# MainMCU.net
KiCad netlist of a schematic drawn in Altium Designer
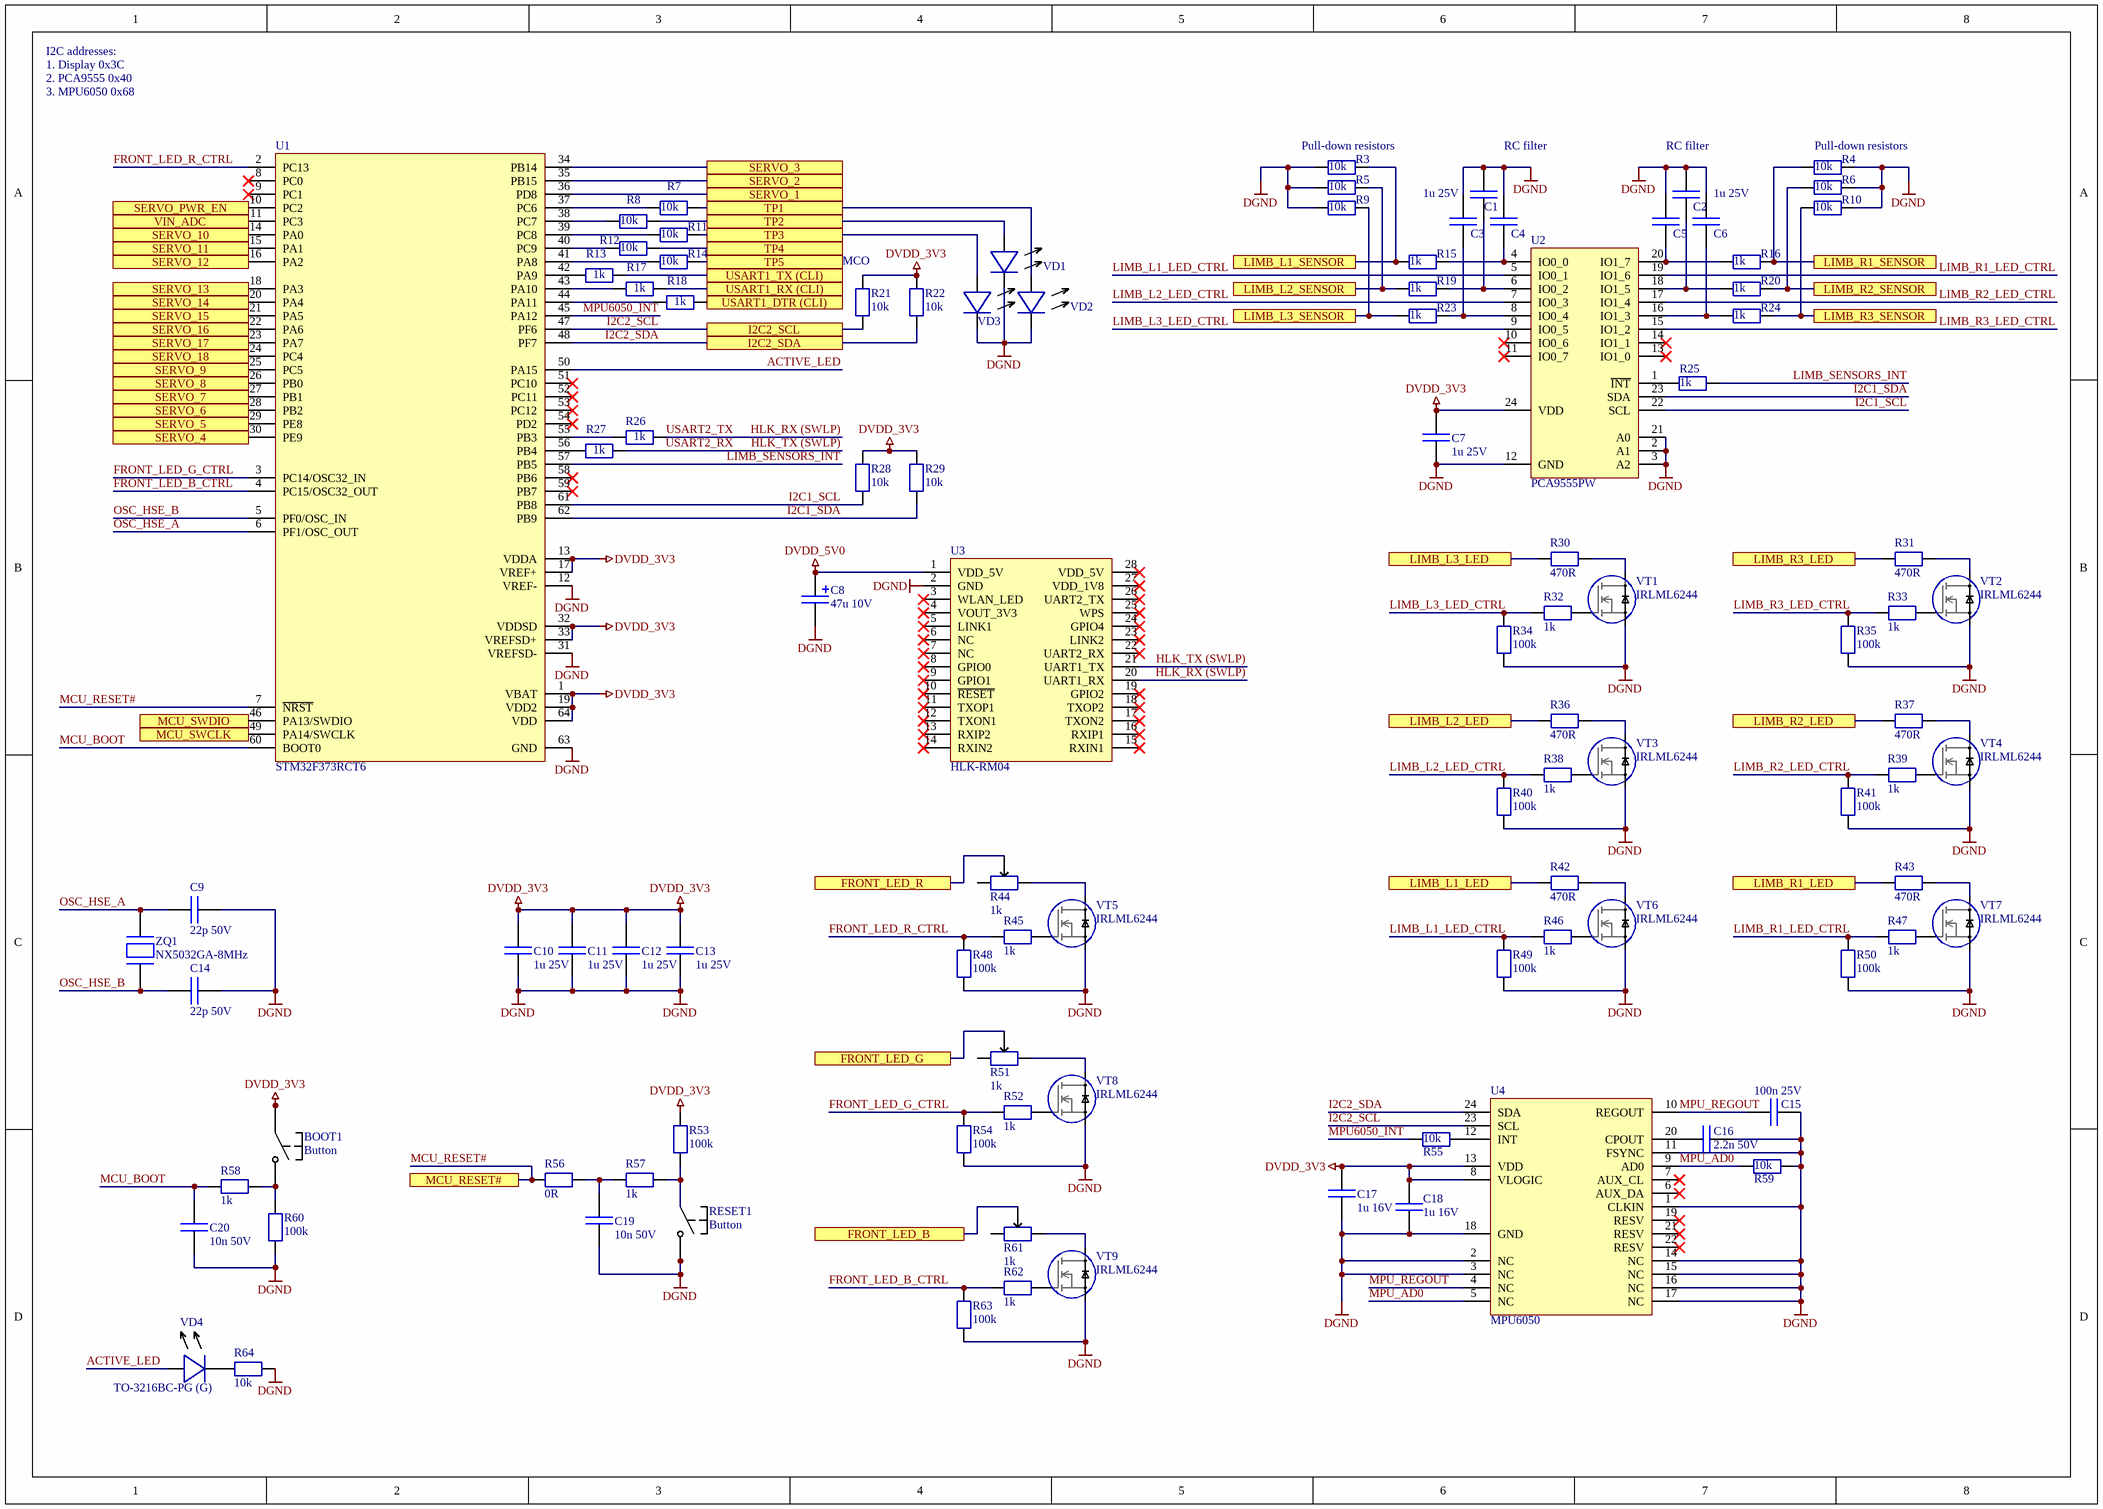
[diagram p0: MainMCU.SchDoc]

(export (version "E")
  (design (tool "Eeschema 10.0.6"))
  (components
    (comp (ref "BOOT1")
      (value "Button")
      (footprint "BUTTON_SMD_3x6")
      (libsource (lib "controls") (part "Button"))
    )
    (comp (ref "C1")
      (value "1u 25V")
      (footprint "C_0603/1608")
      (description "Non-polarized capacitor")
      (libsource (lib "passive") (part "Capacitor"))
    )
    (comp (ref "C2")
      (value "1u 25V")
      (footprint "C_0603/1608")
      (description "Non-polarized capacitor")
      (libsource (lib "passive") (part "Capacitor"))
    )
    (comp (ref "C3")
      (value "1u 25V")
      (footprint "C_0603/1608")
      (description "Non-polarized capacitor")
      (libsource (lib "passive") (part "Capacitor"))
    )
    (comp (ref "C4")
      (value "1u 25V")
      (footprint "C_0603/1608")
      (description "Non-polarized capacitor")
      (libsource (lib "passive") (part "Capacitor"))
    )
    (comp (ref "C5")
      (value "1u 25V")
      (footprint "C_0603/1608")
      (description "Non-polarized capacitor")
      (libsource (lib "passive") (part "Capacitor"))
    )
    (comp (ref "C6")
      (value "1u 25V")
      (footprint "C_0603/1608")
      (description "Non-polarized capacitor")
      (libsource (lib "passive") (part "Capacitor"))
    )
    (comp (ref "C7")
      (value "1u 25V")
      (footprint "C_0603/1608")
      (description "Non-polarized capacitor")
      (libsource (lib "passive") (part "Capacitor"))
    )
    (comp (ref "C8")
      (value "47u 10V")
      (footprint "TECAP_TYPE_B")
      (description "Polarized capacitor")
      (libsource (lib "passive") (part "Capacitor polar"))
    )
    (comp (ref "C9")
      (value "22p 50V")
      (footprint "C_0603/1608")
      (description "Non-polarized capacitor")
      (libsource (lib "passive") (part "Capacitor"))
    )
    (comp (ref "C10")
      (value "1u 25V")
      (footprint "C_0603/1608")
      (description "Non-polarized capacitor")
      (libsource (lib "passive") (part "Capacitor"))
    )
    (comp (ref "C11")
      (value "1u 25V")
      (footprint "C_0603/1608")
      (description "Non-polarized capacitor")
      (libsource (lib "passive") (part "Capacitor"))
    )
    (comp (ref "C12")
      (value "1u 25V")
      (footprint "C_0603/1608")
      (description "Non-polarized capacitor")
      (libsource (lib "passive") (part "Capacitor"))
    )
    (comp (ref "C13")
      (value "1u 25V")
      (footprint "C_0603/1608")
      (description "Non-polarized capacitor")
      (libsource (lib "passive") (part "Capacitor"))
    )
    (comp (ref "C14")
      (value "22p 50V")
      (footprint "C_0603/1608")
      (description "Non-polarized capacitor")
      (libsource (lib "passive") (part "Capacitor"))
    )
    (comp (ref "C15")
      (value "100n 25V")
      (footprint "C_0603/1608")
      (description "Non-polarized capacitor")
      (libsource (lib "passive") (part "Capacitor"))
    )
    (comp (ref "C16")
      (value "2.2n 50V")
      (footprint "C_0603/1608")
      (description "Non-polarized capacitor")
      (libsource (lib "passive") (part "Capacitor"))
    )
    (comp (ref "C17")
      (value "1u 16V")
      (footprint "C_0402/1005")
      (description "Non-polarized capacitor")
      (libsource (lib "passive") (part "Capacitor"))
    )
    (comp (ref "C18")
      (value "1u 16V")
      (footprint "C_0402/1005")
      (description "Non-polarized capacitor")
      (libsource (lib "passive") (part "Capacitor"))
    )
    (comp (ref "C19")
      (value "10n 50V")
      (footprint "C_0603/1608")
      (description "Non-polarized capacitor")
      (libsource (lib "passive") (part "Capacitor"))
    )
    (comp (ref "C20")
      (value "10n 50V")
      (footprint "C_0603/1608")
      (description "Non-polarized capacitor")
      (libsource (lib "passive") (part "Capacitor"))
    )
    (comp (ref "R3")
      (value "10k")
      (footprint "R_0603/1608")
      (description "Resistor")
      (libsource (lib "passive") (part "Resistor"))
    )
    (comp (ref "R4")
      (value "10k")
      (footprint "R_0603/1608")
      (description "Resistor")
      (libsource (lib "passive") (part "Resistor"))
    )
    (comp (ref "R5")
      (value "10k")
      (footprint "R_0603/1608")
      (description "Resistor")
      (libsource (lib "passive") (part "Resistor"))
    )
    (comp (ref "R6")
      (value "10k")
      (footprint "R_0603/1608")
      (description "Resistor")
      (libsource (lib "passive") (part "Resistor"))
    )
    (comp (ref "R7")
      (value "10k")
      (footprint "R_0603/1608")
      (description "Resistor")
      (libsource (lib "passive") (part "Resistor"))
    )
    (comp (ref "R8")
      (value "10k")
      (footprint "R_0603/1608")
      (description "Resistor")
      (libsource (lib "passive") (part "Resistor"))
    )
    (comp (ref "R9")
      (value "10k")
      (footprint "R_0603/1608")
      (description "Resistor")
      (libsource (lib "passive") (part "Resistor"))
    )
    (comp (ref "R10")
      (value "10k")
      (footprint "R_0603/1608")
      (description "Resistor")
      (libsource (lib "passive") (part "Resistor"))
    )
    (comp (ref "R11")
      (value "10k")
      (footprint "R_0603/1608")
      (description "Resistor")
      (libsource (lib "passive") (part "Resistor"))
    )
    (comp (ref "R12")
      (value "10k")
      (footprint "R_0603/1608")
      (description "Resistor")
      (libsource (lib "passive") (part "Resistor"))
    )
    (comp (ref "R13")
      (value "1k")
      (footprint "R_0603/1608")
      (description "Resistor")
      (libsource (lib "passive") (part "Resistor"))
    )
    (comp (ref "R14")
      (value "10k")
      (footprint "R_0603/1608")
      (description "Resistor")
      (libsource (lib "passive") (part "Resistor"))
    )
    (comp (ref "R15")
      (value "1k")
      (footprint "R_0603/1608")
      (description "Resistor")
      (libsource (lib "passive") (part "Resistor"))
    )
    (comp (ref "R16")
      (value "1k")
      (footprint "R_0603/1608")
      (description "Resistor")
      (libsource (lib "passive") (part "Resistor"))
    )
    (comp (ref "R17")
      (value "1k")
      (footprint "R_0603/1608")
      (description "Resistor")
      (libsource (lib "passive") (part "Resistor"))
    )
    (comp (ref "R18")
      (value "1k")
      (footprint "R_0603/1608")
      (description "Resistor")
      (libsource (lib "passive") (part "Resistor"))
    )
    (comp (ref "R19")
      (value "1k")
      (footprint "R_0603/1608")
      (description "Resistor")
      (libsource (lib "passive") (part "Resistor"))
    )
    (comp (ref "R20")
      (value "1k")
      (footprint "R_0603/1608")
      (description "Resistor")
      (libsource (lib "passive") (part "Resistor"))
    )
    (comp (ref "R21")
      (value "10k")
      (footprint "R_0603/1608")
      (description "Resistor")
      (libsource (lib "passive") (part "Resistor"))
    )
    (comp (ref "R22")
      (value "10k")
      (footprint "R_0603/1608")
      (description "Resistor")
      (libsource (lib "passive") (part "Resistor"))
    )
    (comp (ref "R23")
      (value "1k")
      (footprint "R_0603/1608")
      (description "Resistor")
      (libsource (lib "passive") (part "Resistor"))
    )
    (comp (ref "R24")
      (value "1k")
      (footprint "R_0603/1608")
      (description "Resistor")
      (libsource (lib "passive") (part "Resistor"))
    )
    (comp (ref "R25")
      (value "1k")
      (footprint "R_0603/1608")
      (description "Resistor")
      (libsource (lib "passive") (part "Resistor"))
    )
    (comp (ref "R26")
      (value "1k")
      (footprint "R_0603/1608")
      (description "Resistor")
      (libsource (lib "passive") (part "Resistor"))
    )
    (comp (ref "R27")
      (value "1k")
      (footprint "R_0603/1608")
      (description "Resistor")
      (libsource (lib "passive") (part "Resistor"))
    )
    (comp (ref "R28")
      (value "10k")
      (footprint "R_0603/1608")
      (description "Resistor")
      (libsource (lib "passive") (part "Resistor"))
    )
    (comp (ref "R29")
      (value "10k")
      (footprint "R_0603/1608")
      (description "Resistor")
      (libsource (lib "passive") (part "Resistor"))
    )
    (comp (ref "R30")
      (value "470R")
      (footprint "R_0603/1608")
      (description "Resistor")
      (libsource (lib "passive") (part "Resistor"))
    )
    (comp (ref "R31")
      (value "470R")
      (footprint "R_0603/1608")
      (description "Resistor")
      (libsource (lib "passive") (part "Resistor"))
    )
    (comp (ref "R32")
      (value "1k")
      (footprint "R_0603/1608")
      (description "Resistor")
      (libsource (lib "passive") (part "Resistor"))
    )
    (comp (ref "R33")
      (value "1k")
      (footprint "R_0603/1608")
      (description "Resistor")
      (libsource (lib "passive") (part "Resistor"))
    )
    (comp (ref "R34")
      (value "100k")
      (footprint "R_0603/1608")
      (description "Resistor")
      (libsource (lib "passive") (part "Resistor"))
    )
    (comp (ref "R35")
      (value "100k")
      (footprint "R_0603/1608")
      (description "Resistor")
      (libsource (lib "passive") (part "Resistor"))
    )
    (comp (ref "R36")
      (value "470R")
      (footprint "R_0603/1608")
      (description "Resistor")
      (libsource (lib "passive") (part "Resistor"))
    )
    (comp (ref "R37")
      (value "470R")
      (footprint "R_0603/1608")
      (description "Resistor")
      (libsource (lib "passive") (part "Resistor"))
    )
    (comp (ref "R38")
      (value "1k")
      (footprint "R_0603/1608")
      (description "Resistor")
      (libsource (lib "passive") (part "Resistor"))
    )
    (comp (ref "R39")
      (value "1k")
      (footprint "R_0603/1608")
      (description "Resistor")
      (libsource (lib "passive") (part "Resistor"))
    )
    (comp (ref "R40")
      (value "100k")
      (footprint "R_0603/1608")
      (description "Resistor")
      (libsource (lib "passive") (part "Resistor"))
    )
    (comp (ref "R41")
      (value "100k")
      (footprint "R_0603/1608")
      (description "Resistor")
      (libsource (lib "passive") (part "Resistor"))
    )
    (comp (ref "R42")
      (value "470R")
      (footprint "R_0603/1608")
      (description "Resistor")
      (libsource (lib "passive") (part "Resistor"))
    )
    (comp (ref "R43")
      (value "470R")
      (footprint "R_0603/1608")
      (description "Resistor")
      (libsource (lib "passive") (part "Resistor"))
    )
    (comp (ref "R44")
      (value "1k")
      (footprint "R_VAR_3.2x3.2_SMD")
      (description "Resistor variable")
      (libsource (lib "passive") (part "Resistor variable"))
    )
    (comp (ref "R45")
      (value "1k")
      (footprint "R_0603/1608")
      (description "Resistor")
      (libsource (lib "passive") (part "Resistor"))
    )
    (comp (ref "R46")
      (value "1k")
      (footprint "R_0603/1608")
      (description "Resistor")
      (libsource (lib "passive") (part "Resistor"))
    )
    (comp (ref "R47")
      (value "1k")
      (footprint "R_0603/1608")
      (description "Resistor")
      (libsource (lib "passive") (part "Resistor"))
    )
    (comp (ref "R48")
      (value "100k")
      (footprint "R_0603/1608")
      (description "Resistor")
      (libsource (lib "passive") (part "Resistor"))
    )
    (comp (ref "R49")
      (value "100k")
      (footprint "R_0603/1608")
      (description "Resistor")
      (libsource (lib "passive") (part "Resistor"))
    )
    (comp (ref "R50")
      (value "100k")
      (footprint "R_0603/1608")
      (description "Resistor")
      (libsource (lib "passive") (part "Resistor"))
    )
    (comp (ref "R51")
      (value "1k")
      (footprint "R_VAR_3.2x3.2_SMD")
      (description "Resistor variable")
      (libsource (lib "passive") (part "Resistor variable"))
    )
    (comp (ref "R52")
      (value "1k")
      (footprint "R_0603/1608")
      (description "Resistor")
      (libsource (lib "passive") (part "Resistor"))
    )
    (comp (ref "R53")
      (value "100k")
      (footprint "R_0603/1608")
      (description "Resistor")
      (libsource (lib "passive") (part "Resistor"))
    )
    (comp (ref "R54")
      (value "100k")
      (footprint "R_0603/1608")
      (description "Resistor")
      (libsource (lib "passive") (part "Resistor"))
    )
    (comp (ref "R55")
      (value "10k")
      (footprint "R_0603/1608")
      (description "Resistor")
      (libsource (lib "passive") (part "Resistor"))
    )
    (comp (ref "R56")
      (value "0R")
      (footprint "R_0603/1608")
      (description "Resistor")
      (libsource (lib "passive") (part "Resistor"))
    )
    (comp (ref "R57")
      (value "1k")
      (footprint "R_0603/1608")
      (description "Resistor")
      (libsource (lib "passive") (part "Resistor"))
    )
    (comp (ref "R58")
      (value "1k")
      (footprint "R_0603/1608")
      (description "Resistor")
      (libsource (lib "passive") (part "Resistor"))
    )
    (comp (ref "R59")
      (value "10k")
      (footprint "R_0603/1608")
      (description "Resistor")
      (libsource (lib "passive") (part "Resistor"))
    )
    (comp (ref "R60")
      (value "100k")
      (footprint "R_0603/1608")
      (description "Resistor")
      (libsource (lib "passive") (part "Resistor"))
    )
    (comp (ref "R61")
      (value "1k")
      (footprint "R_VAR_3.2x3.2_SMD")
      (description "Resistor variable")
      (libsource (lib "passive") (part "Resistor variable"))
    )
    (comp (ref "R62")
      (value "1k")
      (footprint "R_0603/1608")
      (description "Resistor")
      (libsource (lib "passive") (part "Resistor"))
    )
    (comp (ref "R63")
      (value "100k")
      (footprint "R_0603/1608")
      (description "Resistor")
      (libsource (lib "passive") (part "Resistor"))
    )
    (comp (ref "R64")
      (value "10k")
      (footprint "R_0603/1608")
      (description "Resistor")
      (libsource (lib "passive") (part "Resistor"))
    )
    (comp (ref "RESET1")
      (value "Button")
      (footprint "BUTTON_SMD_3x6")
      (libsource (lib "controls") (part "Button"))
    )
    (comp (ref "U1")
      (value "STM32F373RCT6")
      (footprint "LQFP64")
      (description "32-bit Cortex-M3")
      (libsource (lib "MCU and memory") (part "STM32F373R"))
    )
    (comp (ref "U2")
      (value "PCA9555PW")
      (footprint "SO24_0.65")
      (description "16 bits of General Purpose parallel\r\nInput/Output (GPIO) expansion using I2C")
      (libsource (lib "digital") (part "PCA9555PW"))
    )
    (comp (ref "U3")
      (value "HLK-RM04")
      (footprint "HLK-RM04")
      (description "WIFI-UART bridge")
      (libsource (lib "devices") (part "HLK-RM04"))
    )
    (comp (ref "U4") (value "MPU6050") (footprint "MPU6050") (libsource (lib "devices") (part "MPU6050")))
    (comp (ref "VD1")
      (value "TO-3216BC-PG (G)")
      (footprint "LED_0603/1608")
      (description "LED")
      (libsource (lib "indication") (part "LED"))
    )
    (comp (ref "VD2")
      (value "TO-3216BC-PG (G)")
      (footprint "LED_0603/1608")
      (description "LED")
      (libsource (lib "indication") (part "LED"))
    )
    (comp (ref "VD3")
      (value "TO-3216BC-PG (G)")
      (footprint "LED_0603/1608")
      (description "LED")
      (libsource (lib "indication") (part "LED"))
    )
    (comp (ref "VD4")
      (value "TO-3216BC-PG (G)")
      (footprint "LED_0603/1608")
      (description "LED")
      (libsource (lib "") (part "LED_1"))
    )
    (comp (ref "VT1")
      (value "IRLML6244")
      (footprint "SOT23-3")
      (description "MOSFET N")
      (libsource (lib "active") (part "MOSFET N"))
    )
    (comp (ref "VT2")
      (value "IRLML6244")
      (footprint "SOT23-3")
      (description "MOSFET N")
      (libsource (lib "active") (part "MOSFET N"))
    )
    (comp (ref "VT3")
      (value "IRLML6244")
      (footprint "SOT23-3")
      (description "MOSFET N")
      (libsource (lib "active") (part "MOSFET N"))
    )
    (comp (ref "VT4")
      (value "IRLML6244")
      (footprint "SOT23-3")
      (description "MOSFET N")
      (libsource (lib "active") (part "MOSFET N"))
    )
    (comp (ref "VT5")
      (value "IRLML6244")
      (footprint "SOT23-3")
      (description "MOSFET N")
      (libsource (lib "active") (part "MOSFET N"))
    )
    (comp (ref "VT6")
      (value "IRLML6244")
      (footprint "SOT23-3")
      (description "MOSFET N")
      (libsource (lib "active") (part "MOSFET N"))
    )
    (comp (ref "VT7")
      (value "IRLML6244")
      (footprint "SOT23-3")
      (description "MOSFET N")
      (libsource (lib "active") (part "MOSFET N"))
    )
    (comp (ref "VT8")
      (value "IRLML6244")
      (footprint "SOT23-3")
      (description "MOSFET N")
      (libsource (lib "active") (part "MOSFET N"))
    )
    (comp (ref "VT9")
      (value "IRLML6244")
      (footprint "SOT23-3")
      (description "MOSFET N")
      (libsource (lib "active") (part "MOSFET N"))
    )
    (comp (ref "ZQ1")
      (value "NX5032GA-8MHz")
      (footprint "OSC_2PINS SMD")
      (description "Crystal oscillator")
      (libsource (lib "passive") (part "Crystal oscillator"))
    )
  )
  (nets
    (net (code "1") (name "/ACTIVE_LED") (class "Default")
      (node (ref "U1") (pin "50") (pinfunction "PA15_50") (pintype "passive"))
      (node (ref "VD4") (pin "A") (pinfunction "A_A") (pintype "passive"))
    )
    (net (code "2") (name "/FRONT_LED_B") (class "Default") (node (ref "R61") (pin "2") (pintype "passive")))
    (net (code "3") (name "/FRONT_LED_B_CTRL") (class "Default")
      (node (ref "R62") (pin "2") (pintype "passive"))
      (node (ref "R63") (pin "2") (pintype "passive"))
      (node (ref "U1") (pin "4") (pinfunction "PC15/OSC32_OUT_4") (pintype "passive"))
    )
    (net (code "4") (name "/FRONT_LED_G") (class "Default") (node (ref "R51") (pin "2") (pintype "passive")))
    (net (code "5") (name "/FRONT_LED_G_CTRL") (class "Default")
      (node (ref "R52") (pin "2") (pintype "passive"))
      (node (ref "R54") (pin "2") (pintype "passive"))
      (node (ref "U1") (pin "3") (pinfunction "PC14/OSC32_IN_3") (pintype "passive"))
    )
    (net (code "6") (name "/FRONT_LED_R") (class "Default") (node (ref "R44") (pin "2") (pintype "passive")))
    (net (code "7") (name "/FRONT_LED_R_CTRL") (class "Default")
      (node (ref "R45") (pin "2") (pintype "passive"))
      (node (ref "R48") (pin "2") (pintype "passive"))
      (node (ref "U1") (pin "2") (pinfunction "PC13_2") (pintype "passive"))
    )
    (net (code "8") (name "/HLK_RX (SWLP)") (class "Default")
      (node (ref "R26") (pin "1") (pintype "passive"))
      (node (ref "U3") (pin "20") (pinfunction "UART1_RX_20") (pintype "passive"))
    )
    (net (code "9") (name "/HLK_TX (SWLP)") (class "Default")
      (node (ref "R27") (pin "1") (pintype "passive"))
      (node (ref "U3") (pin "21") (pinfunction "UART1_TX_21") (pintype "passive"))
    )
    (net (code "10") (name "/I2C1_SCL") (class "Default")
      (node (ref "R28") (pin "1") (pintype "passive"))
      (node (ref "U1") (pin "61") (pinfunction "PB8_61") (pintype "passive"))
      (node (ref "U2") (pin "22") (pinfunction "SCL_22") (pintype "passive"))
    )
    (net (code "11") (name "/I2C1_SDA") (class "Default")
      (node (ref "R29") (pin "1") (pintype "passive"))
      (node (ref "U1") (pin "62") (pinfunction "PB9_62") (pintype "passive"))
      (node (ref "U2") (pin "23") (pinfunction "SDA_23") (pintype "passive"))
    )
    (net (code "12") (name "/I2C2_SCL") (class "Default")
      (node (ref "R21") (pin "1") (pintype "passive"))
      (node (ref "U1") (pin "47") (pinfunction "PF6_47") (pintype "passive"))
      (node (ref "U4") (pin "23") (pinfunction "SCL_23") (pintype "passive"))
    )
    (net (code "13") (name "/I2C2_SDA") (class "Default")
      (node (ref "R22") (pin "1") (pintype "passive"))
      (node (ref "U1") (pin "48") (pinfunction "PF7_48") (pintype "passive"))
      (node (ref "U4") (pin "24") (pinfunction "SDA_24") (pintype "passive"))
    )
    (net (code "14") (name "/LIMB_L1_LED") (class "Default") (node (ref "R42") (pin "2") (pintype "passive")))
    (net (code "15") (name "/LIMB_L1_LED_CTRL") (class "Default")
      (node (ref "R46") (pin "2") (pintype "passive"))
      (node (ref "R49") (pin "2") (pintype "passive"))
      (node (ref "U2") (pin "5") (pinfunction "IO0_1_5") (pintype "passive"))
    )
    (net (code "16") (name "/LIMB_L1_SENSOR") (class "Default")
      (node (ref "R15") (pin "1") (pintype "passive"))
      (node (ref "R3") (pin "2") (pintype "passive"))
    )
    (net (code "17") (name "/LIMB_L2_LED") (class "Default") (node (ref "R36") (pin "2") (pintype "passive")))
    (net (code "18") (name "/LIMB_L2_LED_CTRL") (class "Default")
      (node (ref "R38") (pin "2") (pintype "passive"))
      (node (ref "R40") (pin "2") (pintype "passive"))
      (node (ref "U2") (pin "7") (pinfunction "IO0_3_7") (pintype "passive"))
    )
    (net (code "19") (name "/LIMB_L2_SENSOR") (class "Default")
      (node (ref "R19") (pin "1") (pintype "passive"))
      (node (ref "R5") (pin "2") (pintype "passive"))
    )
    (net (code "20") (name "/LIMB_L3_LED") (class "Default") (node (ref "R30") (pin "2") (pintype "passive")))
    (net (code "21") (name "/LIMB_L3_LED_CTRL") (class "Default")
      (node (ref "R32") (pin "2") (pintype "passive"))
      (node (ref "R34") (pin "2") (pintype "passive"))
      (node (ref "U2") (pin "9") (pinfunction "IO0_5_9") (pintype "passive"))
    )
    (net (code "22") (name "/LIMB_L3_SENSOR") (class "Default")
      (node (ref "R23") (pin "1") (pintype "passive"))
      (node (ref "R9") (pin "2") (pintype "passive"))
    )
    (net (code "23") (name "/LIMB_R1_LED") (class "Default") (node (ref "R43") (pin "2") (pintype "passive")))
    (net (code "24") (name "/LIMB_R1_LED_CTRL") (class "Default")
      (node (ref "R47") (pin "2") (pintype "passive"))
      (node (ref "R50") (pin "2") (pintype "passive"))
      (node (ref "U2") (pin "19") (pinfunction "IO1_6_19") (pintype "passive"))
    )
    (net (code "25") (name "/LIMB_R1_SENSOR") (class "Default")
      (node (ref "R16") (pin "2") (pintype "passive"))
      (node (ref "R4") (pin "2") (pintype "passive"))
    )
    (net (code "26") (name "/LIMB_R2_LED") (class "Default") (node (ref "R37") (pin "2") (pintype "passive")))
    (net (code "27") (name "/LIMB_R2_LED_CTRL") (class "Default")
      (node (ref "R39") (pin "2") (pintype "passive"))
      (node (ref "R41") (pin "2") (pintype "passive"))
      (node (ref "U2") (pin "17") (pinfunction "IO1_4_17") (pintype "passive"))
    )
    (net (code "28") (name "/LIMB_R2_SENSOR") (class "Default")
      (node (ref "R20") (pin "2") (pintype "passive"))
      (node (ref "R6") (pin "2") (pintype "passive"))
    )
    (net (code "29") (name "/LIMB_R3_LED") (class "Default") (node (ref "R31") (pin "2") (pintype "passive")))
    (net (code "30") (name "/LIMB_R3_LED_CTRL") (class "Default")
      (node (ref "R33") (pin "2") (pintype "passive"))
      (node (ref "R35") (pin "2") (pintype "passive"))
      (node (ref "U2") (pin "15") (pinfunction "IO1_2_15") (pintype "passive"))
    )
    (net (code "31") (name "/LIMB_R3_SENSOR") (class "Default")
      (node (ref "R10") (pin "2") (pintype "passive"))
      (node (ref "R24") (pin "2") (pintype "passive"))
    )
    (net (code "32") (name "/LIMB_SENSORS_INT") (class "Default")
      (node (ref "R25") (pin "2") (pintype "passive"))
      (node (ref "U1") (pin "57") (pinfunction "PB5_57") (pintype "passive"))
    )
    (net (code "33") (name "/MCU_BOOT") (class "Default")
      (node (ref "C20") (pin "1") (pintype "passive"))
      (node (ref "R58") (pin "2") (pintype "passive"))
      (node (ref "U1") (pin "60") (pinfunction "BOOT0_60") (pintype "passive"))
    )
    (net (code "34") (name "/MCU_RESET#") (class "Default")
      (node (ref "R56") (pin "2") (pintype "passive"))
      (node (ref "U1") (pin "7") (pinfunction "~{NRST}_7") (pintype "passive"))
    )
    (net (code "35") (name "/MCU_SWCLK") (class "Default")
      (node (ref "U1") (pin "49") (pinfunction "PA14/SWCLK_49") (pintype "passive"))
    )
    (net (code "36") (name "/MCU_SWDIO") (class "Default")
      (node (ref "U1") (pin "46") (pinfunction "PA13/SWDIO_46") (pintype "passive"))
    )
    (net (code "37") (name "/MPU6050_INT") (class "Default")
      (node (ref "R55") (pin "2") (pintype "passive"))
      (node (ref "U1") (pin "45") (pinfunction "PA12_45") (pintype "passive"))
    )
    (net (code "38") (name "/MPU_AD0") (class "Default")
      (node (ref "R59") (pin "2") (pintype "passive"))
      (node (ref "U4") (pin "5") (pinfunction "NC_5") (pintype "passive"))
      (node (ref "U4") (pin "9") (pinfunction "AD0_9") (pintype "passive"))
    )
    (net (code "39") (name "/MPU_REGOUT") (class "Default")
      (node (ref "C15") (pin "1") (pintype "passive"))
      (node (ref "U4") (pin "10") (pinfunction "REGOUT_10") (pintype "passive"))
      (node (ref "U4") (pin "4") (pinfunction "NC_4") (pintype "passive"))
    )
    (net (code "40") (name "/OSC_HSE_A") (class "Default")
      (node (ref "C9") (pin "1") (pintype "passive"))
      (node (ref "U1") (pin "6") (pinfunction "PF1/OSC_OUT_6") (pintype "passive"))
      (node (ref "ZQ1") (pin "2") (pintype "passive"))
    )
    (net (code "41") (name "/OSC_HSE_B") (class "Default")
      (node (ref "C14") (pin "1") (pintype "passive"))
      (node (ref "U1") (pin "5") (pinfunction "PF0/OSC_IN_5") (pintype "passive"))
      (node (ref "ZQ1") (pin "1") (pintype "passive"))
    )
    (net (code "42") (name "/SERVO_1") (class "Default")
      (node (ref "U1") (pin "36") (pinfunction "PD8_36") (pintype "passive"))
    )
    (net (code "43") (name "/SERVO_2") (class "Default")
      (node (ref "U1") (pin "35") (pinfunction "PB15_35") (pintype "passive"))
    )
    (net (code "44") (name "/SERVO_3") (class "Default")
      (node (ref "U1") (pin "34") (pinfunction "PB14_34") (pintype "passive"))
    )
    (net (code "45") (name "/SERVO_4") (class "Default")
      (node (ref "U1") (pin "30") (pinfunction "PE9_30") (pintype "passive"))
    )
    (net (code "46") (name "/SERVO_5") (class "Default")
      (node (ref "U1") (pin "29") (pinfunction "PE8_29") (pintype "passive"))
    )
    (net (code "47") (name "/SERVO_6") (class "Default")
      (node (ref "U1") (pin "28") (pinfunction "PB2_28") (pintype "passive"))
    )
    (net (code "48") (name "/SERVO_7") (class "Default")
      (node (ref "U1") (pin "27") (pinfunction "PB1_27") (pintype "passive"))
    )
    (net (code "49") (name "/SERVO_8") (class "Default")
      (node (ref "U1") (pin "26") (pinfunction "PB0_26") (pintype "passive"))
    )
    (net (code "50") (name "/SERVO_9") (class "Default")
      (node (ref "U1") (pin "25") (pinfunction "PC5_25") (pintype "passive"))
    )
    (net (code "51") (name "/SERVO_10") (class "Default")
      (node (ref "U1") (pin "14") (pinfunction "PA0_14") (pintype "passive"))
    )
    (net (code "52") (name "/SERVO_11") (class "Default")
      (node (ref "U1") (pin "15") (pinfunction "PA1_15") (pintype "passive"))
    )
    (net (code "53") (name "/SERVO_12") (class "Default")
      (node (ref "U1") (pin "16") (pinfunction "PA2_16") (pintype "passive"))
    )
    (net (code "54") (name "/SERVO_13") (class "Default")
      (node (ref "U1") (pin "18") (pinfunction "PA3_18") (pintype "passive"))
    )
    (net (code "55") (name "/SERVO_14") (class "Default")
      (node (ref "U1") (pin "20") (pinfunction "PA4_20") (pintype "passive"))
    )
    (net (code "56") (name "/SERVO_15") (class "Default")
      (node (ref "U1") (pin "21") (pinfunction "PA5_21") (pintype "passive"))
    )
    (net (code "57") (name "/SERVO_16") (class "Default")
      (node (ref "U1") (pin "22") (pinfunction "PA6_22") (pintype "passive"))
    )
    (net (code "58") (name "/SERVO_17") (class "Default")
      (node (ref "U1") (pin "23") (pinfunction "PA7_23") (pintype "passive"))
    )
    (net (code "59") (name "/SERVO_18") (class "Default")
      (node (ref "U1") (pin "24") (pinfunction "PC4_24") (pintype "passive"))
    )
    (net (code "60") (name "/SERVO_PWR_EN") (class "Default")
      (node (ref "U1") (pin "10") (pinfunction "PC2_10") (pintype "passive"))
    )
    (net (code "61") (name "/TP1") (class "Default")
      (node (ref "R7") (pin "2") (pintype "passive"))
      (node (ref "VD2") (pin "A") (pinfunction "A_A") (pintype "passive"))
    )
    (net (code "62") (name "/TP2") (class "Default")
      (node (ref "R8") (pin "2") (pintype "passive"))
      (node (ref "VD1") (pin "A") (pinfunction "A_A") (pintype "passive"))
    )
    (net (code "63") (name "/TP3") (class "Default")
      (node (ref "R11") (pin "2") (pintype "passive"))
      (node (ref "VD3") (pin "A") (pinfunction "A_A") (pintype "passive"))
    )
    (net (code "64") (name "/TP4") (class "Default") (node (ref "R12") (pin "2") (pintype "passive")))
    (net (code "65") (name "/TP5") (class "Default") (node (ref "R14") (pin "2") (pintype "passive")))
    (net (code "66") (name "/USART1_DTR (CLI)") (class "Default")
      (node (ref "R18") (pin "1") (pintype "passive"))
    )
    (net (code "67") (name "/USART1_RX (CLI)") (class "Default")
      (node (ref "R17") (pin "1") (pintype "passive"))
    )
    (net (code "68") (name "/USART1_TX (CLI)") (class "Default")
      (node (ref "R13") (pin "1") (pintype "passive"))
    )
    (net (code "69") (name "/VIN_ADC") (class "Default")
      (node (ref "U1") (pin "11") (pinfunction "PC3_11") (pintype "passive"))
    )
    (net (code "70") (name "DGND") (class "Default")
      (node (ref "C1") (pin "1") (pintype "passive"))
      (node (ref "C10") (pin "2") (pintype "passive"))
      (node (ref "C11") (pin "2") (pintype "passive"))
      (node (ref "C12") (pin "2") (pintype "passive"))
      (node (ref "C13") (pin "2") (pintype "passive"))
      (node (ref "C14") (pin "2") (pintype "passive"))
      (node (ref "C15") (pin "2") (pintype "passive"))
      (node (ref "C16") (pin "2") (pintype "passive"))
      (node (ref "C17") (pin "2") (pintype "passive"))
      (node (ref "C18") (pin "2") (pintype "passive"))
      (node (ref "C19") (pin "2") (pintype "passive"))
      (node (ref "C2") (pin "1") (pintype "passive"))
      (node (ref "C20") (pin "2") (pintype "passive"))
      (node (ref "C3") (pin "1") (pintype "passive"))
      (node (ref "C4") (pin "1") (pintype "passive"))
      (node (ref "C5") (pin "1") (pintype "passive"))
      (node (ref "C6") (pin "1") (pintype "passive"))
      (node (ref "C7") (pin "2") (pintype "passive"))
      (node (ref "C8") (pin "2") (pinfunction "NEG_2") (pintype "passive"))
      (node (ref "C9") (pin "2") (pintype "passive"))
      (node (ref "R10") (pin "1") (pintype "passive"))
      (node (ref "R3") (pin "1") (pintype "passive"))
      (node (ref "R34") (pin "1") (pintype "passive"))
      (node (ref "R35") (pin "1") (pintype "passive"))
      (node (ref "R4") (pin "1") (pintype "passive"))
      (node (ref "R40") (pin "1") (pintype "passive"))
      (node (ref "R41") (pin "1") (pintype "passive"))
      (node (ref "R48") (pin "1") (pintype "passive"))
      (node (ref "R49") (pin "1") (pintype "passive"))
      (node (ref "R5") (pin "1") (pintype "passive"))
      (node (ref "R50") (pin "1") (pintype "passive"))
      (node (ref "R54") (pin "1") (pintype "passive"))
      (node (ref "R59") (pin "1") (pintype "passive"))
      (node (ref "R6") (pin "1") (pintype "passive"))
      (node (ref "R60") (pin "2") (pintype "passive"))
      (node (ref "R63") (pin "1") (pintype "passive"))
      (node (ref "R64") (pin "1") (pintype "passive"))
      (node (ref "R9") (pin "1") (pintype "passive"))
      (node (ref "RESET1") (pin "2") (pinfunction "2_2") (pintype "passive"))
      (node (ref "RESET1") (pin "4") (pinfunction "4_4") (pintype "passive"))
      (node (ref "U1") (pin "12") (pinfunction "VREF-_12") (pintype "passive"))
      (node (ref "U1") (pin "31") (pinfunction "VREFSD-_31") (pintype "passive"))
      (node (ref "U1") (pin "63") (pinfunction "GND_63") (pintype "passive"))
      (node (ref "U2") (pin "12") (pinfunction "GND_12") (pintype "passive"))
      (node (ref "U2") (pin "2") (pinfunction "A1_2") (pintype "passive"))
      (node (ref "U2") (pin "21") (pinfunction "A0_21") (pintype "passive"))
      (node (ref "U2") (pin "3") (pinfunction "A2_3") (pintype "passive"))
      (node (ref "U3") (pin "2") (pinfunction "GND_2") (pintype "passive"))
      (node (ref "U4") (pin "1") (pinfunction "CLKIN_1") (pintype "passive"))
      (node (ref "U4") (pin "11") (pinfunction "FSYNC_11") (pintype "passive"))
      (node (ref "U4") (pin "14") (pinfunction "NC_14") (pintype "passive"))
      (node (ref "U4") (pin "15") (pinfunction "NC_15") (pintype "passive"))
      (node (ref "U4") (pin "16") (pinfunction "NC_16") (pintype "passive"))
      (node (ref "U4") (pin "17") (pinfunction "NC_17") (pintype "passive"))
      (node (ref "U4") (pin "18") (pinfunction "GND_18") (pintype "passive"))
      (node (ref "U4") (pin "2") (pinfunction "NC_2") (pintype "passive"))
      (node (ref "U4") (pin "3") (pinfunction "NC_3") (pintype "passive"))
      (node (ref "VD1") (pin "C") (pinfunction "C_C") (pintype "passive"))
      (node (ref "VD2") (pin "C") (pinfunction "C_C") (pintype "passive"))
      (node (ref "VD3") (pin "C") (pinfunction "C_C") (pintype "passive"))
      (node (ref "VT1") (pin "S") (pintype "passive"))
      (node (ref "VT2") (pin "S") (pintype "passive"))
      (node (ref "VT3") (pin "S") (pintype "passive"))
      (node (ref "VT4") (pin "S") (pintype "passive"))
      (node (ref "VT5") (pin "S") (pintype "passive"))
      (node (ref "VT6") (pin "S") (pintype "passive"))
      (node (ref "VT7") (pin "S") (pintype "passive"))
      (node (ref "VT8") (pin "S") (pintype "passive"))
      (node (ref "VT9") (pin "S") (pintype "passive"))
    )
    (net (code "71") (name "DVDD_3V3") (class "Default")
      (node (ref "BOOT1") (pin "1") (pinfunction "1_1") (pintype "passive"))
      (node (ref "BOOT1") (pin "3") (pinfunction "3_3") (pintype "passive"))
      (node (ref "C10") (pin "1") (pintype "passive"))
      (node (ref "C11") (pin "1") (pintype "passive"))
      (node (ref "C12") (pin "1") (pintype "passive"))
      (node (ref "C13") (pin "1") (pintype "passive"))
      (node (ref "C17") (pin "1") (pintype "passive"))
      (node (ref "C18") (pin "1") (pintype "passive"))
      (node (ref "C7") (pin "1") (pintype "passive"))
      (node (ref "R21") (pin "2") (pintype "passive"))
      (node (ref "R22") (pin "2") (pintype "passive"))
      (node (ref "R28") (pin "2") (pintype "passive"))
      (node (ref "R29") (pin "2") (pintype "passive"))
      (node (ref "R53") (pin "1") (pintype "passive"))
      (node (ref "U1") (pin "1") (pinfunction "VBAT_1") (pintype "passive"))
      (node (ref "U1") (pin "13") (pinfunction "VDDA_13") (pintype "passive"))
      (node (ref "U1") (pin "17") (pinfunction "VREF+_17") (pintype "passive"))
      (node (ref "U1") (pin "19") (pinfunction "VDD2_19") (pintype "passive"))
      (node (ref "U1") (pin "32") (pinfunction "VDDSD_32") (pintype "passive"))
      (node (ref "U1") (pin "33") (pinfunction "VREFSD+_33") (pintype "passive"))
      (node (ref "U1") (pin "64") (pinfunction "VDD_64") (pintype "passive"))
      (node (ref "U2") (pin "24") (pinfunction "VDD_24") (pintype "passive"))
      (node (ref "U4") (pin "13") (pinfunction "VDD_13") (pintype "passive"))
      (node (ref "U4") (pin "8") (pinfunction "VLOGIC_8") (pintype "passive"))
    )
    (net (code "72") (name "DVDD_5V0") (class "Default")
      (node (ref "C8") (pin "1") (pinfunction "POS_1") (pintype "passive"))
      (node (ref "U3") (pin "1") (pinfunction "VDD_5V_1") (pintype "passive"))
    )
    (net (code "73") (name "Net-(BOOT1-Pad2)") (class "Default")
      (node (ref "BOOT1") (pin "2") (pinfunction "2_2") (pintype "passive"))
      (node (ref "BOOT1") (pin "4") (pinfunction "4_4") (pintype "passive"))
      (node (ref "R58") (pin "1") (pintype "passive"))
      (node (ref "R60") (pin "1") (pintype "passive"))
    )
    (net (code "74") (name "Net-(C19-Pad1)") (class "Default")
      (node (ref "C19") (pin "1") (pintype "passive"))
      (node (ref "R56") (pin "1") (pintype "passive"))
      (node (ref "R57") (pin "2") (pintype "passive"))
    )
    (net (code "75") (name "Net-(R30-Pad1)") (class "Default")
      (node (ref "R30") (pin "1") (pintype "passive"))
      (node (ref "VT1") (pin "D") (pintype "passive"))
    )
    (net (code "76") (name "Net-(R31-Pad1)") (class "Default")
      (node (ref "R31") (pin "1") (pintype "passive"))
      (node (ref "VT2") (pin "D") (pintype "passive"))
    )
    (net (code "77") (name "Net-(R32-Pad1)") (class "Default")
      (node (ref "R32") (pin "1") (pintype "passive"))
      (node (ref "VT1") (pin "G") (pintype "passive"))
    )
    (net (code "78") (name "Net-(R33-Pad1)") (class "Default")
      (node (ref "R33") (pin "1") (pintype "passive"))
      (node (ref "VT2") (pin "G") (pintype "passive"))
    )
    (net (code "79") (name "Net-(R36-Pad1)") (class "Default")
      (node (ref "R36") (pin "1") (pintype "passive"))
      (node (ref "VT3") (pin "D") (pintype "passive"))
    )
    (net (code "80") (name "Net-(R37-Pad1)") (class "Default")
      (node (ref "R37") (pin "1") (pintype "passive"))
      (node (ref "VT4") (pin "D") (pintype "passive"))
    )
    (net (code "81") (name "Net-(R38-Pad1)") (class "Default")
      (node (ref "R38") (pin "1") (pintype "passive"))
      (node (ref "VT3") (pin "G") (pintype "passive"))
    )
    (net (code "82") (name "Net-(R39-Pad1)") (class "Default")
      (node (ref "R39") (pin "1") (pintype "passive"))
      (node (ref "VT4") (pin "G") (pintype "passive"))
    )
    (net (code "83") (name "Net-(R42-Pad1)") (class "Default")
      (node (ref "R42") (pin "1") (pintype "passive"))
      (node (ref "VT6") (pin "D") (pintype "passive"))
    )
    (net (code "84") (name "Net-(R43-Pad1)") (class "Default")
      (node (ref "R43") (pin "1") (pintype "passive"))
      (node (ref "VT7") (pin "D") (pintype "passive"))
    )
    (net (code "85") (name "Net-(R44-Pad3)") (class "Default")
      (node (ref "R44") (pin "3") (pintype "passive"))
      (node (ref "VT5") (pin "D") (pintype "passive"))
    )
    (net (code "86") (name "Net-(R45-Pad1)") (class "Default")
      (node (ref "R45") (pin "1") (pintype "passive"))
      (node (ref "VT5") (pin "G") (pintype "passive"))
    )
    (net (code "87") (name "Net-(R46-Pad1)") (class "Default")
      (node (ref "R46") (pin "1") (pintype "passive"))
      (node (ref "VT6") (pin "G") (pintype "passive"))
    )
    (net (code "88") (name "Net-(R47-Pad1)") (class "Default")
      (node (ref "R47") (pin "1") (pintype "passive"))
      (node (ref "VT7") (pin "G") (pintype "passive"))
    )
    (net (code "89") (name "Net-(R51-Pad3)") (class "Default")
      (node (ref "R51") (pin "3") (pintype "passive"))
      (node (ref "VT8") (pin "D") (pintype "passive"))
    )
    (net (code "90") (name "Net-(R52-Pad1)") (class "Default")
      (node (ref "R52") (pin "1") (pintype "passive"))
      (node (ref "VT8") (pin "G") (pintype "passive"))
    )
    (net (code "91") (name "Net-(R53-Pad2)") (class "Default")
      (node (ref "R53") (pin "2") (pintype "passive"))
      (node (ref "R57") (pin "1") (pintype "passive"))
      (node (ref "RESET1") (pin "1") (pinfunction "1_1") (pintype "passive"))
      (node (ref "RESET1") (pin "3") (pinfunction "3_3") (pintype "passive"))
    )
    (net (code "92") (name "Net-(R61-Pad3)") (class "Default")
      (node (ref "R61") (pin "3") (pintype "passive"))
      (node (ref "VT9") (pin "D") (pintype "passive"))
    )
    (net (code "93") (name "Net-(R62-Pad1)") (class "Default")
      (node (ref "R62") (pin "1") (pintype "passive"))
      (node (ref "VT9") (pin "G") (pintype "passive"))
    )
    (net (code "94") (name "Net-(R64-Pad2)") (class "Default")
      (node (ref "R64") (pin "2") (pintype "passive"))
      (node (ref "VD4") (pin "C") (pinfunction "C_C") (pintype "passive"))
    )
    (net (code "95") (name "Net-(U1-PA8)") (class "Default")
      (node (ref "R14") (pin "1") (pintype "passive"))
      (node (ref "U1") (pin "41") (pinfunction "PA8_41") (pintype "passive"))
    )
    (net (code "96") (name "Net-(U1-PA9)") (class "Default")
      (node (ref "R13") (pin "2") (pintype "passive"))
      (node (ref "U1") (pin "42") (pinfunction "PA9_42") (pintype "passive"))
    )
    (net (code "97") (name "Net-(U1-PA10)") (class "Default")
      (node (ref "R17") (pin "2") (pintype "passive"))
      (node (ref "U1") (pin "43") (pinfunction "PA10_43") (pintype "passive"))
    )
    (net (code "98") (name "Net-(U1-PA11)") (class "Default")
      (node (ref "R18") (pin "2") (pintype "passive"))
      (node (ref "U1") (pin "44") (pinfunction "PA11_44") (pintype "passive"))
    )
    (net (code "99") (name "Net-(U1-PB3)") (class "Default")
      (node (ref "R26") (pin "2") (pintype "passive"))
      (node (ref "U1") (pin "55") (pinfunction "PB3_55") (pintype "passive"))
    )
    (net (code "100") (name "Net-(U1-PB4)") (class "Default")
      (node (ref "R27") (pin "2") (pintype "passive"))
      (node (ref "U1") (pin "56") (pinfunction "PB4_56") (pintype "passive"))
    )
    (net (code "101") (name "Net-(U1-PC6)") (class "Default")
      (node (ref "R7") (pin "1") (pintype "passive"))
      (node (ref "U1") (pin "37") (pinfunction "PC6_37") (pintype "passive"))
    )
    (net (code "102") (name "Net-(U1-PC7)") (class "Default")
      (node (ref "R8") (pin "1") (pintype "passive"))
      (node (ref "U1") (pin "38") (pinfunction "PC7_38") (pintype "passive"))
    )
    (net (code "103") (name "Net-(U1-PC8)") (class "Default")
      (node (ref "R11") (pin "1") (pintype "passive"))
      (node (ref "U1") (pin "39") (pinfunction "PC8_39") (pintype "passive"))
    )
    (net (code "104") (name "Net-(U1-PC9)") (class "Default")
      (node (ref "R12") (pin "1") (pintype "passive"))
      (node (ref "U1") (pin "40") (pinfunction "PC9_40") (pintype "passive"))
    )
    (net (code "105") (name "Net-(U2-IO0_0)") (class "Default")
      (node (ref "C4") (pin "2") (pintype "passive"))
      (node (ref "R15") (pin "2") (pintype "passive"))
      (node (ref "U2") (pin "4") (pinfunction "IO0_0_4") (pintype "passive"))
    )
    (net (code "106") (name "Net-(U2-IO0_2)") (class "Default")
      (node (ref "C1") (pin "2") (pintype "passive"))
      (node (ref "R19") (pin "2") (pintype "passive"))
      (node (ref "U2") (pin "6") (pinfunction "IO0_2_6") (pintype "passive"))
    )
    (net (code "107") (name "Net-(U2-IO0_4)") (class "Default")
      (node (ref "C3") (pin "2") (pintype "passive"))
      (node (ref "R23") (pin "2") (pintype "passive"))
      (node (ref "U2") (pin "8") (pinfunction "IO0_4_8") (pintype "passive"))
    )
    (net (code "108") (name "Net-(U2-IO1_3)") (class "Default")
      (node (ref "C6") (pin "2") (pintype "passive"))
      (node (ref "R24") (pin "1") (pintype "passive"))
      (node (ref "U2") (pin "16") (pinfunction "IO1_3_16") (pintype "passive"))
    )
    (net (code "109") (name "Net-(U2-IO1_5)") (class "Default")
      (node (ref "C2") (pin "2") (pintype "passive"))
      (node (ref "R20") (pin "1") (pintype "passive"))
      (node (ref "U2") (pin "18") (pinfunction "IO1_5_18") (pintype "passive"))
    )
    (net (code "110") (name "Net-(U2-IO1_7)") (class "Default")
      (node (ref "C5") (pin "2") (pintype "passive"))
      (node (ref "R16") (pin "1") (pintype "passive"))
      (node (ref "U2") (pin "20") (pinfunction "IO1_7_20") (pintype "passive"))
    )
    (net (code "111") (name "Net-(U2-~{INT})") (class "Default")
      (node (ref "R25") (pin "1") (pintype "passive"))
      (node (ref "U2") (pin "1") (pinfunction "~{INT}_1") (pintype "passive"))
    )
    (net (code "112") (name "Net-(U4-CPOUT)") (class "Default")
      (node (ref "C16") (pin "1") (pintype "passive"))
      (node (ref "U4") (pin "20") (pinfunction "CPOUT_20") (pintype "passive"))
    )
    (net (code "113") (name "Net-(U4-INT)") (class "Default")
      (node (ref "R55") (pin "1") (pintype "passive"))
      (node (ref "U4") (pin "12") (pinfunction "INT_12") (pintype "passive"))
    )
    (net (code "114") (name "unconnected-(R44-Pad1)") (class "Default")
      (node (ref "R44") (pin "1") (pintype "passive"))
    )
    (net (code "115") (name "unconnected-(R51-Pad1)") (class "Default")
      (node (ref "R51") (pin "1") (pintype "passive"))
    )
    (net (code "116") (name "unconnected-(R61-Pad1)") (class "Default")
      (node (ref "R61") (pin "1") (pintype "passive"))
    )
    (net (code "117") (name "unconnected-(U1-EP-Pad0)") (class "Default")
      (node (ref "U1") (pin "0") (pinfunction "EP_0") (pintype "passive"))
    )
    (net (code "118") (name "unconnected-(U1-PB6-Pad58)") (class "Default")
      (node (ref "U1") (pin "58") (pinfunction "PB6_58") (pintype "passive+no_connect"))
    )
    (net (code "119") (name "unconnected-(U1-PB7-Pad59)") (class "Default")
      (node (ref "U1") (pin "59") (pinfunction "PB7_59") (pintype "passive+no_connect"))
    )
    (net (code "120") (name "unconnected-(U1-PC0-Pad8)") (class "Default")
      (node (ref "U1") (pin "8") (pinfunction "PC0_8") (pintype "passive+no_connect"))
    )
    (net (code "121") (name "unconnected-(U1-PC1-Pad9)") (class "Default")
      (node (ref "U1") (pin "9") (pinfunction "PC1_9") (pintype "passive+no_connect"))
    )
    (net (code "122") (name "unconnected-(U1-PC10-Pad51)") (class "Default")
      (node (ref "U1") (pin "51") (pinfunction "PC10_51") (pintype "passive+no_connect"))
    )
    (net (code "123") (name "unconnected-(U1-PC11-Pad52)") (class "Default")
      (node (ref "U1") (pin "52") (pinfunction "PC11_52") (pintype "passive+no_connect"))
    )
    (net (code "124") (name "unconnected-(U1-PC12-Pad53)") (class "Default")
      (node (ref "U1") (pin "53") (pinfunction "PC12_53") (pintype "passive+no_connect"))
    )
    (net (code "125") (name "unconnected-(U1-PD2-Pad54)") (class "Default")
      (node (ref "U1") (pin "54") (pinfunction "PD2_54") (pintype "passive+no_connect"))
    )
    (net (code "126") (name "unconnected-(U2-IO0_6-Pad10)") (class "Default")
      (node (ref "U2") (pin "10") (pinfunction "IO0_6_10") (pintype "passive+no_connect"))
    )
    (net (code "127") (name "unconnected-(U2-IO0_7-Pad11)") (class "Default")
      (node (ref "U2") (pin "11") (pinfunction "IO0_7_11") (pintype "passive+no_connect"))
    )
    (net (code "128") (name "unconnected-(U2-IO1_0-Pad13)") (class "Default")
      (node (ref "U2") (pin "13") (pinfunction "IO1_0_13") (pintype "passive+no_connect"))
    )
    (net (code "129") (name "unconnected-(U2-IO1_1-Pad14)") (class "Default")
      (node (ref "U2") (pin "14") (pinfunction "IO1_1_14") (pintype "passive+no_connect"))
    )
    (net (code "130") (name "unconnected-(U3-EP-Pad0)") (class "Default")
      (node (ref "U3") (pin "0") (pinfunction "EP_0") (pintype "passive"))
    )
    (net (code "131") (name "unconnected-(U3-GPIO0-Pad8)") (class "Default")
      (node (ref "U3") (pin "8") (pinfunction "GPIO0_8") (pintype "passive+no_connect"))
    )
    (net (code "132") (name "unconnected-(U3-GPIO1-Pad9)") (class "Default")
      (node (ref "U3") (pin "9") (pinfunction "GPIO1_9") (pintype "passive+no_connect"))
    )
    (net (code "133") (name "unconnected-(U3-GPIO2-Pad19)") (class "Default")
      (node (ref "U3") (pin "19") (pinfunction "GPIO2_19") (pintype "passive+no_connect"))
    )
    (net (code "134") (name "unconnected-(U3-GPIO4-Pad24)") (class "Default")
      (node (ref "U3") (pin "24") (pinfunction "GPIO4_24") (pintype "passive+no_connect"))
    )
    (net (code "135") (name "unconnected-(U3-LINK1-Pad5)") (class "Default")
      (node (ref "U3") (pin "5") (pinfunction "LINK1_5") (pintype "passive+no_connect"))
    )
    (net (code "136") (name "unconnected-(U3-LINK2-Pad23)") (class "Default")
      (node (ref "U3") (pin "23") (pinfunction "LINK2_23") (pintype "passive+no_connect"))
    )
    (net (code "137") (name "unconnected-(U3-NC-Pad6)") (class "Default")
      (node (ref "U3") (pin "6") (pinfunction "NC_6") (pintype "passive+no_connect"))
    )
    (net (code "138") (name "unconnected-(U3-NC-Pad7)") (class "Default")
      (node (ref "U3") (pin "7") (pinfunction "NC_7") (pintype "passive+no_connect"))
    )
    (net (code "139") (name "unconnected-(U3-RXIN1-Pad15)") (class "Default")
      (node (ref "U3") (pin "15") (pinfunction "RXIN1_15") (pintype "passive+no_connect"))
    )
    (net (code "140") (name "unconnected-(U3-RXIN2-Pad14)") (class "Default")
      (node (ref "U3") (pin "14") (pinfunction "RXIN2_14") (pintype "passive+no_connect"))
    )
    (net (code "141") (name "unconnected-(U3-RXIP1-Pad16)") (class "Default")
      (node (ref "U3") (pin "16") (pinfunction "RXIP1_16") (pintype "passive+no_connect"))
    )
    (net (code "142") (name "unconnected-(U3-RXIP2-Pad13)") (class "Default")
      (node (ref "U3") (pin "13") (pinfunction "RXIP2_13") (pintype "passive+no_connect"))
    )
    (net (code "143") (name "unconnected-(U3-TXON1-Pad12)") (class "Default")
      (node (ref "U3") (pin "12") (pinfunction "TXON1_12") (pintype "passive+no_connect"))
    )
    (net (code "144") (name "unconnected-(U3-TXON2-Pad17)") (class "Default")
      (node (ref "U3") (pin "17") (pinfunction "TXON2_17") (pintype "passive+no_connect"))
    )
    (net (code "145") (name "unconnected-(U3-TXOP1-Pad11)") (class "Default")
      (node (ref "U3") (pin "11") (pinfunction "TXOP1_11") (pintype "passive+no_connect"))
    )
    (net (code "146") (name "unconnected-(U3-TXOP2-Pad18)") (class "Default")
      (node (ref "U3") (pin "18") (pinfunction "TXOP2_18") (pintype "passive+no_connect"))
    )
    (net (code "147") (name "unconnected-(U3-UART2_RX-Pad22)") (class "Default")
      (node (ref "U3") (pin "22") (pinfunction "UART2_RX_22") (pintype "passive+no_connect"))
    )
    (net (code "148") (name "unconnected-(U3-UART2_TX-Pad26)") (class "Default")
      (node (ref "U3") (pin "26") (pinfunction "UART2_TX_26") (pintype "passive+no_connect"))
    )
    (net (code "149") (name "unconnected-(U3-VDD_1V8-Pad27)") (class "Default")
      (node (ref "U3") (pin "27") (pinfunction "VDD_1V8_27") (pintype "passive+no_connect"))
    )
    (net (code "150") (name "unconnected-(U3-VDD_5V-Pad28)") (class "Default")
      (node (ref "U3") (pin "28") (pinfunction "VDD_5V_28") (pintype "passive+no_connect"))
    )
    (net (code "151") (name "unconnected-(U3-VOUT_3V3-Pad4)") (class "Default")
      (node (ref "U3") (pin "4") (pinfunction "VOUT_3V3_4") (pintype "passive+no_connect"))
    )
    (net (code "152") (name "unconnected-(U3-WLAN_LED-Pad3)") (class "Default")
      (node (ref "U3") (pin "3") (pinfunction "WLAN_LED_3") (pintype "passive+no_connect"))
    )
    (net (code "153") (name "unconnected-(U3-WPS-Pad25)") (class "Default")
      (node (ref "U3") (pin "25") (pinfunction "WPS_25") (pintype "passive+no_connect"))
    )
    (net (code "154") (name "unconnected-(U3-~{RESET}-Pad10)") (class "Default")
      (node (ref "U3") (pin "10") (pinfunction "~{RESET}_10") (pintype "passive+no_connect"))
    )
    (net (code "155") (name "unconnected-(U4-AUX_CL-Pad7)") (class "Default")
      (node (ref "U4") (pin "7") (pinfunction "AUX_CL_7") (pintype "passive+no_connect"))
    )
    (net (code "156") (name "unconnected-(U4-AUX_DA-Pad6)") (class "Default")
      (node (ref "U4") (pin "6") (pinfunction "AUX_DA_6") (pintype "passive+no_connect"))
    )
    (net (code "157") (name "unconnected-(U4-EP-Pad0)") (class "Default")
      (node (ref "U4") (pin "0") (pinfunction "EP_0") (pintype "passive"))
    )
    (net (code "158") (name "unconnected-(U4-RESV-Pad19)") (class "Default")
      (node (ref "U4") (pin "19") (pinfunction "RESV_19") (pintype "passive+no_connect"))
    )
    (net (code "159") (name "unconnected-(U4-RESV-Pad21)") (class "Default")
      (node (ref "U4") (pin "21") (pinfunction "RESV_21") (pintype "passive+no_connect"))
    )
    (net (code "160") (name "unconnected-(U4-RESV-Pad22)") (class "Default")
      (node (ref "U4") (pin "22") (pinfunction "RESV_22") (pintype "passive+no_connect"))
    )
  )
)
